# D2.net
KiCad netlist of a schematic drawn in Altium Designer
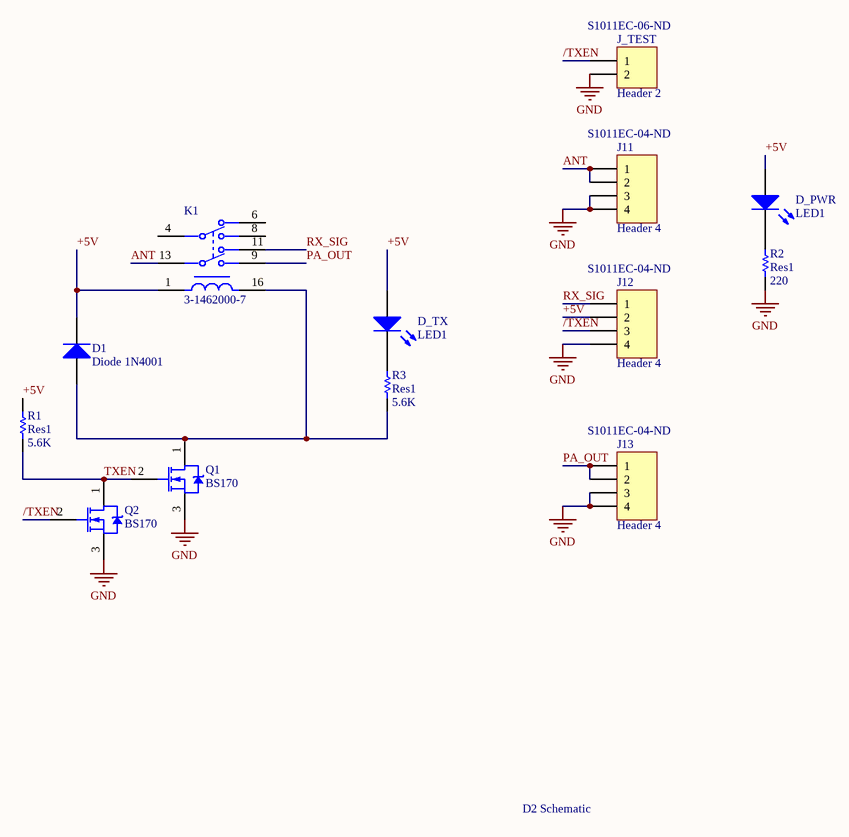
[diagram p0: D2.SchDoc]

(export (version "E")
  (design (tool "Eeschema 10.0.6"))
  (components
    (comp (ref "D1")
      (value "Diode 1N4001")
      (footprint "DO-41")
      (description "1 Amp General Purpose Rectifier")
      (fields (field (name "PUBLISHER") "Altium Limited"))
      (libsource (lib "Miscellaneous Devices") (part "Diode 1N4001"))
    )
    (comp (ref "D_PWR")
      (value "LED1")
      (footprint "LED-1")
      (description "Typical RED GaAs LED")
      (fields (field (name "PUBLISHER") "Altium Limited"))
      (libsource (lib "Miscellaneous Devices") (part "LED1"))
    )
    (comp (ref "D_TX")
      (value "LED1")
      (footprint "LED-1")
      (description "Typical RED GaAs LED")
      (fields (field (name "PUBLISHER") "Altium Limited"))
      (libsource (lib "Miscellaneous Devices") (part "LED1"))
    )
    (comp (ref "J11")
      (value "Header 4")
      (footprint "HDR1X4")
      (description "Conn Header Vert 4POS 2.54MM")
      (fields
        (field (name "SUPPLIER PART NUMBER 1") "S1011EC-04-ND")
        (field (name "MANUFACTURER") "Sullins")
        (field (name "MANUFACTURER PART NUMBER") "PRPC004SAAN-RC")
        (field (name "PUBLISHER") "Altium Limited")
      )
      (libsource (lib "Miscellaneous Connectors") (part "Header 4"))
    )
    (comp (ref "J12")
      (value "Header 4")
      (footprint "HDR1X4")
      (description "Conn Header Vert 4POS 2.54MM")
      (fields
        (field (name "SUPPLIER PART NUMBER 1") "S1011EC-04-ND")
        (field (name "MANUFACTURER") "Sullins")
        (field (name "MANUFACTURER PART NUMBER") "PRPC004SAAN-RC")
        (field (name "PUBLISHER") "Altium Limited")
      )
      (libsource (lib "Miscellaneous Connectors") (part "Header 4"))
    )
    (comp (ref "J13")
      (value "Header 4")
      (footprint "HDR1X4")
      (description "Conn Header Vert 4POS 2.54MM")
      (fields
        (field (name "SUPPLIER PART NUMBER 1") "S1011EC-04-ND")
        (field (name "MANUFACTURER") "Sullins")
        (field (name "MANUFACTURER PART NUMBER") "PRPC004SAAN-RC")
        (field (name "PUBLISHER") "Altium Limited")
      )
      (libsource (lib "Miscellaneous Connectors") (part "Header 4"))
    )
    (comp (ref "J_TEST")
      (value "Header 2")
      (footprint "HDR1X2")
      (description "Conn Header .100\" Sngl Str 6POS")
      (fields
        (field (name "SUPPLIER PART NUMBER 1") "S1011EC-06-ND")
        (field (name "MANUFACTURER") "Sullins")
        (field (name "MANUFACTURER PART NUMBER") "PRPC006SAAN-RC")
        (field (name "PUBLISHER") "Altium Limited")
      )
      (libsource (lib "Miscellaneous Connectors") (part "Header 2"))
    )
    (comp (ref "K1")
      (value "3-1462000-7")
      (footprint "FP-3-1462000-7-MFG")
      (description "RELAY TELECOM DPDT 2A 12VDC")
      (fields
        (field (name "MANUFACTURER") "TE Connectivity")
        (field (name "OCTOPART") "https://octopart.com/3-1462000-7-te+connectivity-40092230")
      )
      (libsource (lib "Altium Content Vault") (part "84d1d39ad31b6eb1c8aed030b26f258"))
    )
    (comp (ref "Q1")
      (value "BS170")
      (footprint "ONSC-TO-92-3-29-11")
      (description "Small Signal MOSFET, 500 mA, 60 V, N-Channel, 3-Pin TO-92, Bulk Box")
      (fields (field (name "MANUFACTURER") "On Semiconductor"))
      (libsource (lib "Altium Content Vault") (part "ONSC-NMOS-D1G2S3-3"))
    )
    (comp (ref "Q2")
      (value "BS170")
      (footprint "ONSC-TO-92-3-29-11")
      (description "Small Signal MOSFET, 500 mA, 60 V, N-Channel, 3-Pin TO-92, Bulk Box")
      (fields (field (name "MANUFACTURER") "On Semiconductor"))
      (libsource (lib "Altium Content Vault") (part "ONSC-NMOS-D1G2S3-3"))
    )
    (comp (ref "R1")
      (value "Res1")
      (footprint "AXIAL-0.1-RES")
      (description "Resistor")
      (fields
        (field (name "ALTIUM_VALUE") "5.6K")
        (field (name "MANUFACTURER PART NUMBER") "CFR-25JB-52-5K6")
        (field (name "TOLERANCE") "0.05")
        (field (name "PUBLISHER") "Altium Limited")
      )
      (libsource (lib "ECE295-Resistors-TH") (part "RES 5.6K OHM 5% 1/4W AXIAL"))
    )
    (comp (ref "R2")
      (value "Res1")
      (footprint "AXIAL-0.1-RES")
      (description "Resistor")
      (fields
        (field (name "ALTIUM_VALUE") "220")
        (field (name "MANUFACTURER PART NUMBER") "CFR-25JB-52-270R")
        (field (name "TOLERANCE") "0.05")
        (field (name "PUBLISHER") "Altium Limited")
      )
      (libsource (lib "ECE295-Resistors-TH") (part "RES 270 OHM 5% 1/4W AXIAL"))
    )
    (comp (ref "R3")
      (value "Res1")
      (footprint "AXIAL-0.1-RES")
      (description "Resistor")
      (fields
        (field (name "ALTIUM_VALUE") "5.6K")
        (field (name "MANUFACTURER PART NUMBER") "CFR-25JB-52-5K6")
        (field (name "TOLERANCE") "0.05")
        (field (name "PUBLISHER") "Altium Limited")
      )
      (libsource (lib "ECE295-Resistors-TH") (part "RES 5.6K OHM 5% 1/4W AXIAL"))
    )
  )
  (nets
    (net (code "1") (name "/+5V") (class "Default")
      (node (ref "D1") (pin "2") (pinfunction "K_2") (pintype "passive"))
      (node (ref "D_PWR") (pin "1") (pinfunction "A_1") (pintype "passive"))
      (node (ref "D_TX") (pin "1") (pinfunction "A_1") (pintype "passive"))
      (node (ref "J12") (pin "2") (pinfunction "2_2") (pintype "passive"))
      (node (ref "K1") (pin "1") (pinfunction "1_1") (pintype "passive"))
      (node (ref "R1") (pin "1") (pinfunction "1_1") (pintype "passive"))
    )
    (net (code "2") (name "/ANT") (class "Default")
      (node (ref "J11") (pin "1") (pinfunction "1_1") (pintype "passive"))
      (node (ref "J11") (pin "2") (pinfunction "2_2") (pintype "passive"))
      (node (ref "K1") (pin "13") (pinfunction "13_13") (pintype "passive"))
    )
    (net (code "3") (name "/PA_OUT") (class "Default")
      (node (ref "J13") (pin "1") (pinfunction "1_1") (pintype "passive"))
      (node (ref "J13") (pin "2") (pinfunction "2_2") (pintype "passive"))
      (node (ref "K1") (pin "9") (pinfunction "9_9") (pintype "passive"))
    )
    (net (code "4") (name "/RX_SIG") (class "Default")
      (node (ref "J12") (pin "1") (pinfunction "1_1") (pintype "passive"))
      (node (ref "K1") (pin "11") (pinfunction "11_11") (pintype "passive"))
    )
    (net (code "5") (name "/TXEN") (class "Default")
      (node (ref "Q1") (pin "2") (pinfunction "G_2") (pintype "passive"))
      (node (ref "Q2") (pin "1") (pinfunction "D_1") (pintype "passive"))
      (node (ref "R1") (pin "2") (pinfunction "2_2") (pintype "passive"))
    )
    (net (code "6") (name "/{slash}TXEN") (class "Default")
      (node (ref "J12") (pin "3") (pinfunction "3_3") (pintype "passive"))
      (node (ref "J_TEST") (pin "1") (pinfunction "1_1") (pintype "passive"))
      (node (ref "Q2") (pin "2") (pinfunction "G_2") (pintype "passive"))
    )
    (net (code "7") (name "GND") (class "Default")
      (node (ref "J11") (pin "3") (pinfunction "3_3") (pintype "passive"))
      (node (ref "J11") (pin "4") (pinfunction "4_4") (pintype "passive"))
      (node (ref "J12") (pin "4") (pinfunction "4_4") (pintype "passive"))
      (node (ref "J13") (pin "3") (pinfunction "3_3") (pintype "passive"))
      (node (ref "J13") (pin "4") (pinfunction "4_4") (pintype "passive"))
      (node (ref "J_TEST") (pin "2") (pinfunction "2_2") (pintype "passive"))
      (node (ref "Q1") (pin "3") (pinfunction "S_3") (pintype "passive"))
      (node (ref "Q2") (pin "3") (pinfunction "S_3") (pintype "passive"))
      (node (ref "R2") (pin "1") (pinfunction "1_1") (pintype "passive"))
    )
    (net (code "8") (name "Net-(D1-A)") (class "Default")
      (node (ref "D1") (pin "1") (pinfunction "A_1") (pintype "passive"))
      (node (ref "K1") (pin "16") (pinfunction "16_16") (pintype "passive"))
      (node (ref "Q1") (pin "1") (pinfunction "D_1") (pintype "passive"))
      (node (ref "R3") (pin "2") (pinfunction "2_2") (pintype "passive"))
    )
    (net (code "9") (name "Net-(D_PWR-K)") (class "Default")
      (node (ref "D_PWR") (pin "2") (pinfunction "K_2") (pintype "passive"))
      (node (ref "R2") (pin "2") (pinfunction "2_2") (pintype "passive"))
    )
    (net (code "10") (name "Net-(D_TX-K)") (class "Default")
      (node (ref "D_TX") (pin "2") (pinfunction "K_2") (pintype "passive"))
      (node (ref "R3") (pin "1") (pinfunction "1_1") (pintype "passive"))
    )
    (net (code "11") (name "unconnected-(K1-Pad4)") (class "Default")
      (node (ref "K1") (pin "4") (pinfunction "4_4") (pintype "passive"))
    )
    (net (code "12") (name "unconnected-(K1-Pad6)") (class "Default")
      (node (ref "K1") (pin "6") (pinfunction "6_6") (pintype "passive"))
    )
    (net (code "13") (name "unconnected-(K1-Pad8)") (class "Default")
      (node (ref "K1") (pin "8") (pinfunction "8_8") (pintype "passive"))
    )
  )
)
